# Logic_Board.net
KiCad netlist of a schematic drawn in EAGLE
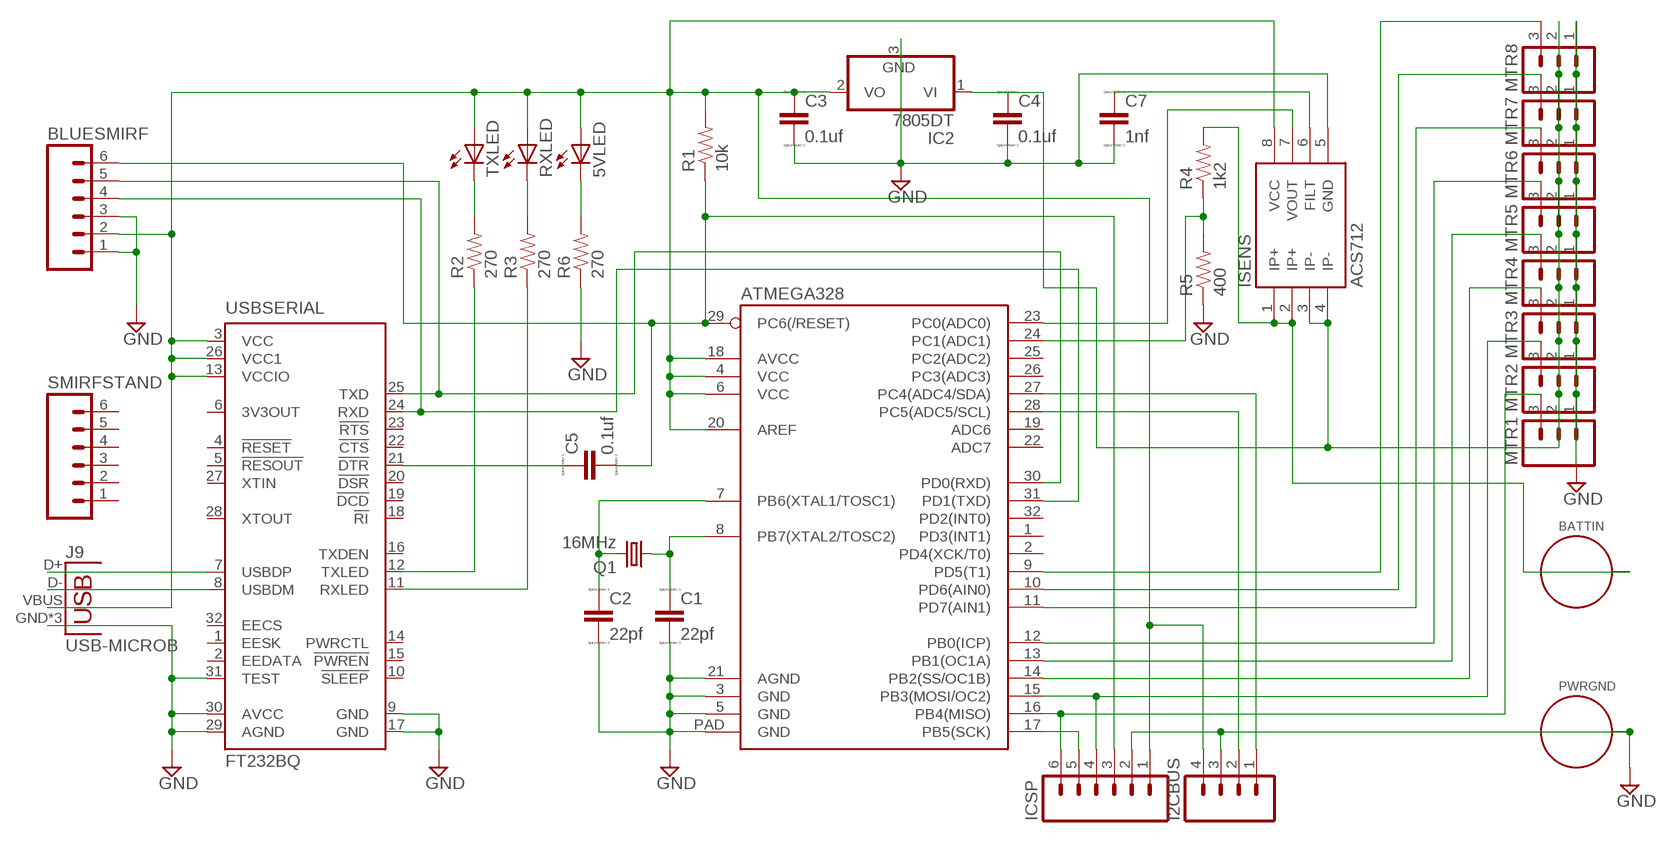
[diagram p0: schematic, sheet 1]

(export (version "E")
  (design (tool "Eeschema 10.0.6"))
  (components
    (comp (ref "5VLED")
      (value "LEDCHIPLED_0805")
      (footprint "eagle-import:CHIPLED_0805")
      (libsource (lib "eagle-import") (part "LEDCHIPLED_0805"))
    )
    (comp (ref "ATMEGA328")
      (value "ATMEGA328P_MLFMLF32")
      (footprint "eagle-import:MLF32-PAD")
      (libsource (lib "eagle-import") (part "ATMEGA328P_MLFMLF32"))
    )
    (comp (ref "BATTIN")
      (value "STANDOFF_ELECTRICAL")
      (footprint "eagle-import:STANDOFF-ELECTRICAL")
      (libsource (lib "eagle-import") (part "STANDOFF_ELECTRICAL"))
    )
    (comp (ref "BLUESMIRF")
      (value "M06NO_SILK_YES_STOP")
      (footprint "eagle-import:1X06_NO_SILK_YES_STOP")
      (libsource (lib "eagle-import") (part "M06NO_SILK_YES_STOP"))
    )
    (comp (ref "C1")
      (value "22pf")
      (footprint "eagle-import:C0805")
      (libsource (lib "eagle-import") (part "C"))
    )
    (comp (ref "C2")
      (value "22pf")
      (footprint "eagle-import:C0805")
      (libsource (lib "eagle-import") (part "C"))
    )
    (comp (ref "C3")
      (value "0.1uf")
      (footprint "eagle-import:C0805")
      (libsource (lib "eagle-import") (part "C"))
    )
    (comp (ref "C4")
      (value "0.1uf")
      (footprint "eagle-import:C0805")
      (libsource (lib "eagle-import") (part "C"))
    )
    (comp (ref "C5")
      (value "0.1uf")
      (footprint "eagle-import:C0805")
      (libsource (lib "eagle-import") (part "C"))
    )
    (comp (ref "C7")
      (value "1nf")
      (footprint "eagle-import:C0805")
      (libsource (lib "eagle-import") (part "C"))
    )
    (comp (ref "I2CBUS")
      (value "M04NO_SILK_ALL_ROUND")
      (footprint "eagle-import:1X04_NO_SILK_ALL_ROUND")
      (libsource (lib "eagle-import") (part "M04NO_SILK_ALL_ROUND"))
    )
    (comp (ref "IC2")
      (value "7805DT")
      (footprint "eagle-import:TO252")
      (libsource (lib "eagle-import") (part "78DT05"))
    )
    (comp (ref "ICSP")
      (value "M06NO_SILK_YES_STOP")
      (footprint "eagle-import:1X06_NO_SILK_YES_STOP")
      (libsource (lib "eagle-import") (part "M06NO_SILK_YES_STOP"))
    )
    (comp (ref "ISENS")
      (value "ACS712")
      (footprint "eagle-import:SO08")
      (libsource (lib "eagle-import") (part "ACS712"))
    )
    (comp (ref "J9")
      (value "USB-MICROB")
      (footprint "eagle-import:USB-MICROB")
      (libsource (lib "eagle-import") (part "USB-MICROB"))
    )
    (comp (ref "MTR1")
      (value "M03PTH")
      (footprint "eagle-import:1X03")
      (libsource (lib "eagle-import") (part "M03PTH"))
    )
    (comp (ref "MTR2")
      (value "M03PTH")
      (footprint "eagle-import:1X03")
      (libsource (lib "eagle-import") (part "M03PTH"))
    )
    (comp (ref "MTR3")
      (value "M03PTH")
      (footprint "eagle-import:1X03")
      (libsource (lib "eagle-import") (part "M03PTH"))
    )
    (comp (ref "MTR4")
      (value "M03PTH")
      (footprint "eagle-import:1X03")
      (libsource (lib "eagle-import") (part "M03PTH"))
    )
    (comp (ref "MTR5")
      (value "M03PTH")
      (footprint "eagle-import:1X03")
      (libsource (lib "eagle-import") (part "M03PTH"))
    )
    (comp (ref "MTR6")
      (value "M03PTH")
      (footprint "eagle-import:1X03")
      (libsource (lib "eagle-import") (part "M03PTH"))
    )
    (comp (ref "MTR7")
      (value "M03PTH")
      (footprint "eagle-import:1X03")
      (libsource (lib "eagle-import") (part "M03PTH"))
    )
    (comp (ref "MTR8")
      (value "M03PTH")
      (footprint "eagle-import:1X03")
      (libsource (lib "eagle-import") (part "M03PTH"))
    )
    (comp (ref "PWRGND")
      (value "STANDOFF_ELECTRICAL")
      (footprint "eagle-import:STANDOFF-ELECTRICAL")
      (libsource (lib "eagle-import") (part "STANDOFF_ELECTRICAL"))
    )
    (comp (ref "Q1")
      (value "16MHz")
      (footprint "eagle-import:HC49U-V")
      (libsource (lib "eagle-import") (part "CRYSTALHC49U-V"))
    )
    (comp (ref "R1")
      (value "10k")
      (footprint "eagle-import:0805")
      (libsource (lib "eagle-import") (part "RESISTOR0805-RES"))
    )
    (comp (ref "R2")
      (value "270")
      (footprint "eagle-import:0805")
      (libsource (lib "eagle-import") (part "RESISTOR0805-RES"))
    )
    (comp (ref "R3")
      (value "270")
      (footprint "eagle-import:0805")
      (libsource (lib "eagle-import") (part "RESISTOR0805-RES"))
    )
    (comp (ref "R4")
      (value "1k2")
      (footprint "eagle-import:0805")
      (libsource (lib "eagle-import") (part "RESISTOR0805-RES"))
    )
    (comp (ref "R5")
      (value "400")
      (footprint "eagle-import:0805")
      (libsource (lib "eagle-import") (part "RESISTOR0805-RES"))
    )
    (comp (ref "R6")
      (value "270")
      (footprint "eagle-import:0805")
      (libsource (lib "eagle-import") (part "RESISTOR0805-RES"))
    )
    (comp (ref "RXLED")
      (value "LEDCHIPLED_0805")
      (footprint "eagle-import:CHIPLED_0805")
      (libsource (lib "eagle-import") (part "LEDCHIPLED_0805"))
    )
    (comp (ref "SMIRFSTAND")
      (value "M06NO_SILK_YES_STOP")
      (footprint "eagle-import:1X06_NO_SILK_YES_STOP")
      (libsource (lib "eagle-import") (part "M06NO_SILK_YES_STOP"))
    )
    (comp (ref "TXLED")
      (value "LEDCHIPLED_0805")
      (footprint "eagle-import:CHIPLED_0805")
      (libsource (lib "eagle-import") (part "LEDCHIPLED_0805"))
    )
    (comp (ref "USBSERIAL")
      (value "FT232BQ")
      (footprint "eagle-import:QFN32")
      (libsource (lib "eagle-import") (part "FT232BQ"))
    )
  )
  (nets
    (net (code "1") (name "GND") (class "Default")
      (node (ref "ATMEGA328") (pin "21") (pinfunction "AGND_21") (pintype "bidirectional"))
      (node (ref "ATMEGA328") (pin "3") (pinfunction "GND_3") (pintype "bidirectional"))
      (node (ref "ATMEGA328") (pin "5") (pinfunction "GND_5") (pintype "bidirectional"))
      (node (ref "ATMEGA328") (pin "PAD") (pinfunction "GND_PAD") (pintype "bidirectional"))
      (node (ref "BLUESMIRF") (pin "1") (pinfunction "1_1") (pintype "passive"))
      (node (ref "BLUESMIRF") (pin "3") (pinfunction "3_3") (pintype "passive"))
      (node (ref "C1") (pin "2") (pinfunction "2_2") (pintype "passive"))
      (node (ref "C2") (pin "2") (pinfunction "2_2") (pintype "passive"))
      (node (ref "C3") (pin "2") (pinfunction "2_2") (pintype "passive"))
      (node (ref "C4") (pin "2") (pinfunction "2_2") (pintype "passive"))
      (node (ref "C7") (pin "2") (pinfunction "2_2") (pintype "passive"))
      (node (ref "I2CBUS") (pin "3") (pinfunction "3_3") (pintype "passive"))
      (node (ref "IC2") (pin "3") (pinfunction "GND_3") (pintype "passive"))
      (node (ref "ICSP") (pin "2") (pinfunction "2_2") (pintype "passive"))
      (node (ref "ISENS") (pin "5") (pinfunction "GND_5") (pintype "bidirectional"))
      (node (ref "J9") (pin "GND") (pinfunction "GND_GND") (pintype "bidirectional"))
      (node (ref "J9") (pin "MT1") (pinfunction "GND_MT1") (pintype "bidirectional"))
      (node (ref "J9") (pin "MT2") (pinfunction "GND_MT2") (pintype "bidirectional"))
      (node (ref "MTR1") (pin "1") (pinfunction "1_1") (pintype "passive"))
      (node (ref "MTR2") (pin "1") (pinfunction "1_1") (pintype "passive"))
      (node (ref "MTR3") (pin "1") (pinfunction "1_1") (pintype "passive"))
      (node (ref "MTR4") (pin "1") (pinfunction "1_1") (pintype "passive"))
      (node (ref "MTR5") (pin "1") (pinfunction "1_1") (pintype "passive"))
      (node (ref "MTR6") (pin "1") (pinfunction "1_1") (pintype "passive"))
      (node (ref "MTR7") (pin "1") (pinfunction "1_1") (pintype "passive"))
      (node (ref "MTR8") (pin "1") (pinfunction "1_1") (pintype "passive"))
      (node (ref "PWRGND") (pin "P1") (pinfunction "P$1_P1") (pintype "bidirectional"))
      (node (ref "R5") (pin "1") (pinfunction "1_1") (pintype "passive"))
      (node (ref "R6") (pin "1") (pinfunction "1_1") (pintype "passive"))
      (node (ref "USBSERIAL") (pin "17") (pinfunction "GND_17") (pintype "power_in"))
      (node (ref "USBSERIAL") (pin "29") (pinfunction "AGND_29") (pintype "power_in"))
      (node (ref "USBSERIAL") (pin "30") (pinfunction "AVCC_30") (pintype "power_in"))
      (node (ref "USBSERIAL") (pin "31") (pinfunction "TEST_31") (pintype "input"))
      (node (ref "USBSERIAL") (pin "9") (pinfunction "GND_9") (pintype "power_in"))
    )
    (net (code "2") (name "Net-(5VLED-PadC)") (class "Default")
      (node (ref "5VLED") (pin "C") (pinfunction "C_C") (pintype "passive"))
      (node (ref "R6") (pin "2") (pinfunction "2_2") (pintype "passive"))
    )
    (net (code "3") (name "Net-(ATMEGA328-AREF)") (class "Default")
      (node (ref "5VLED") (pin "A") (pinfunction "A_A") (pintype "passive"))
      (node (ref "ATMEGA328") (pin "18") (pinfunction "AVCC_18") (pintype "bidirectional"))
      (node (ref "ATMEGA328") (pin "20") (pinfunction "AREF_20") (pintype "bidirectional"))
      (node (ref "ATMEGA328") (pin "4") (pinfunction "VCC_4") (pintype "bidirectional"))
      (node (ref "ATMEGA328") (pin "6") (pinfunction "VCC_6") (pintype "bidirectional"))
      (node (ref "BLUESMIRF") (pin "2") (pinfunction "2_2") (pintype "passive"))
      (node (ref "C3") (pin "1") (pinfunction "1_1") (pintype "passive"))
      (node (ref "I2CBUS") (pin "4") (pinfunction "4_4") (pintype "passive"))
      (node (ref "IC2") (pin "2") (pinfunction "VO_2") (pintype "passive"))
      (node (ref "ICSP") (pin "1") (pinfunction "1_1") (pintype "passive"))
      (node (ref "ISENS") (pin "8") (pinfunction "VCC_8") (pintype "bidirectional"))
      (node (ref "J9") (pin "VBUS") (pinfunction "VBUS_VBUS") (pintype "bidirectional"))
      (node (ref "R1") (pin "2") (pinfunction "2_2") (pintype "passive"))
      (node (ref "RXLED") (pin "A") (pinfunction "A_A") (pintype "passive"))
      (node (ref "TXLED") (pin "A") (pinfunction "A_A") (pintype "passive"))
      (node (ref "USBSERIAL") (pin "13") (pinfunction "VCCIO_13") (pintype "power_in"))
      (node (ref "USBSERIAL") (pin "26") (pinfunction "VCC1_26") (pintype "power_in"))
      (node (ref "USBSERIAL") (pin "3") (pinfunction "VCC_3") (pintype "power_in"))
    )
    (net (code "4") (name "Net-(ATMEGA328-PB0(ICP))") (class "Default")
      (node (ref "ATMEGA328") (pin "12") (pinfunction "PB0(ICP)_12") (pintype "bidirectional"))
      (node (ref "MTR5") (pin "3") (pinfunction "3_3") (pintype "passive"))
    )
    (net (code "5") (name "Net-(ATMEGA328-PB1(OC1A))") (class "Default")
      (node (ref "ATMEGA328") (pin "13") (pinfunction "PB1(OC1A)_13") (pintype "bidirectional"))
      (node (ref "MTR4") (pin "3") (pinfunction "3_3") (pintype "passive"))
    )
    (net (code "6") (name "Net-(ATMEGA328-PB2(SS{slash}OC1B))") (class "Default")
      (node (ref "ATMEGA328") (pin "14") (pinfunction "PB2(SS/OC1B)_14") (pintype "bidirectional"))
      (node (ref "MTR3") (pin "3") (pinfunction "3_3") (pintype "passive"))
    )
    (net (code "7") (name "Net-(ATMEGA328-PB3(MOSI{slash}OC2))") (class "Default")
      (node (ref "ATMEGA328") (pin "15") (pinfunction "PB3(MOSI/OC2)_15") (pintype "bidirectional"))
      (node (ref "ICSP") (pin "4") (pinfunction "4_4") (pintype "passive"))
      (node (ref "MTR2") (pin "3") (pinfunction "3_3") (pintype "passive"))
    )
    (net (code "8") (name "Net-(ATMEGA328-PB4(MISO))") (class "Default")
      (node (ref "ATMEGA328") (pin "16") (pinfunction "PB4(MISO)_16") (pintype "bidirectional"))
      (node (ref "ICSP") (pin "6") (pinfunction "6_6") (pintype "passive"))
      (node (ref "MTR1") (pin "3") (pinfunction "3_3") (pintype "passive"))
    )
    (net (code "9") (name "Net-(ATMEGA328-PB5(SCK))") (class "Default")
      (node (ref "ATMEGA328") (pin "17") (pinfunction "PB5(SCK)_17") (pintype "bidirectional"))
      (node (ref "ICSP") (pin "5") (pinfunction "5_5") (pintype "passive"))
    )
    (net (code "10") (name "Net-(ATMEGA328-PB6(XTAL1{slash}TOSC1))") (class "Default")
      (node (ref "ATMEGA328") (pin "7") (pinfunction "PB6(XTAL1/TOSC1)_7") (pintype "bidirectional"))
      (node (ref "C2") (pin "1") (pinfunction "1_1") (pintype "passive"))
      (node (ref "Q1") (pin "2") (pinfunction "2_2") (pintype "passive"))
    )
    (net (code "11") (name "Net-(ATMEGA328-PB7(XTAL2{slash}TOSC2))") (class "Default")
      (node (ref "ATMEGA328") (pin "8") (pinfunction "PB7(XTAL2/TOSC2)_8") (pintype "bidirectional"))
      (node (ref "C1") (pin "1") (pinfunction "1_1") (pintype "passive"))
      (node (ref "Q1") (pin "1") (pinfunction "1_1") (pintype "passive"))
    )
    (net (code "12") (name "Net-(ATMEGA328-PC0(ADC0))") (class "Default")
      (node (ref "ATMEGA328") (pin "23") (pinfunction "PC0(ADC0)_23") (pintype "bidirectional"))
      (node (ref "ISENS") (pin "7") (pinfunction "VOUT_7") (pintype "bidirectional"))
    )
    (net (code "13") (name "Net-(ATMEGA328-PC1(ADC1))") (class "Default")
      (node (ref "ATMEGA328") (pin "24") (pinfunction "PC1(ADC1)_24") (pintype "bidirectional"))
      (node (ref "R4") (pin "1") (pinfunction "1_1") (pintype "passive"))
      (node (ref "R5") (pin "2") (pinfunction "2_2") (pintype "passive"))
    )
    (net (code "14") (name "Net-(ATMEGA328-PC4(ADC4{slash}SDA))") (class "Default")
      (node (ref "ATMEGA328") (pin "27") (pinfunction "PC4(ADC4/SDA)_27") (pintype "bidirectional"))
      (node (ref "I2CBUS") (pin "1") (pinfunction "1_1") (pintype "passive"))
    )
    (net (code "15") (name "Net-(ATMEGA328-PC5(ADC5{slash}SCL))") (class "Default")
      (node (ref "ATMEGA328") (pin "28") (pinfunction "PC5(ADC5/SCL)_28") (pintype "bidirectional"))
      (node (ref "I2CBUS") (pin "2") (pinfunction "2_2") (pintype "passive"))
    )
    (net (code "16") (name "Net-(ATMEGA328-PC6({slash}RESET))") (class "Default")
      (node (ref "ATMEGA328") (pin "29") (pinfunction "PC6(/RESET)_29") (pintype "bidirectional"))
      (node (ref "BLUESMIRF") (pin "6") (pinfunction "6_6") (pintype "passive"))
      (node (ref "C5") (pin "2") (pinfunction "2_2") (pintype "passive"))
      (node (ref "ICSP") (pin "3") (pinfunction "3_3") (pintype "passive"))
      (node (ref "R1") (pin "1") (pinfunction "1_1") (pintype "passive"))
    )
    (net (code "17") (name "Net-(ATMEGA328-PD0(RXD))") (class "Default")
      (node (ref "ATMEGA328") (pin "30") (pinfunction "PD0(RXD)_30") (pintype "bidirectional"))
      (node (ref "BLUESMIRF") (pin "5") (pinfunction "5_5") (pintype "passive"))
      (node (ref "USBSERIAL") (pin "25") (pinfunction "TXD_25") (pintype "output"))
    )
    (net (code "18") (name "Net-(ATMEGA328-PD1(TXD))") (class "Default")
      (node (ref "ATMEGA328") (pin "31") (pinfunction "PD1(TXD)_31") (pintype "bidirectional"))
      (node (ref "BLUESMIRF") (pin "4") (pinfunction "4_4") (pintype "passive"))
      (node (ref "USBSERIAL") (pin "24") (pinfunction "RXD_24") (pintype "input"))
    )
    (net (code "19") (name "Net-(ATMEGA328-PD5(T1))") (class "Default")
      (node (ref "ATMEGA328") (pin "9") (pinfunction "PD5(T1)_9") (pintype "bidirectional"))
      (node (ref "MTR8") (pin "3") (pinfunction "3_3") (pintype "passive"))
    )
    (net (code "20") (name "Net-(ATMEGA328-PD6(AIN0))") (class "Default")
      (node (ref "ATMEGA328") (pin "10") (pinfunction "PD6(AIN0)_10") (pintype "bidirectional"))
      (node (ref "MTR7") (pin "3") (pinfunction "3_3") (pintype "passive"))
    )
    (net (code "21") (name "Net-(ATMEGA328-PD7(AIN1))") (class "Default")
      (node (ref "ATMEGA328") (pin "11") (pinfunction "PD7(AIN1)_11") (pintype "bidirectional"))
      (node (ref "MTR6") (pin "3") (pinfunction "3_3") (pintype "passive"))
    )
    (net (code "22") (name "Net-(BATTIN-P$1)") (class "Default")
      (node (ref "BATTIN") (pin "P1") (pinfunction "P$1_P1") (pintype "bidirectional"))
      (node (ref "ISENS") (pin "1") (pinfunction "IP+_1") (pintype "bidirectional"))
      (node (ref "ISENS") (pin "2") (pinfunction "IP+_2") (pintype "bidirectional"))
      (node (ref "R4") (pin "2") (pinfunction "2_2") (pintype "passive"))
    )
    (net (code "23") (name "Net-(IC2-VI)") (class "Default")
      (node (ref "C4") (pin "1") (pinfunction "1_1") (pintype "passive"))
      (node (ref "IC2") (pin "1") (pinfunction "VI_1") (pintype "input"))
      (node (ref "ISENS") (pin "3") (pinfunction "IP-_3") (pintype "bidirectional"))
      (node (ref "ISENS") (pin "4") (pinfunction "IP-_4") (pintype "bidirectional"))
      (node (ref "MTR1") (pin "2") (pinfunction "2_2") (pintype "passive"))
      (node (ref "MTR2") (pin "2") (pinfunction "2_2") (pintype "passive"))
      (node (ref "MTR3") (pin "2") (pinfunction "2_2") (pintype "passive"))
      (node (ref "MTR4") (pin "2") (pinfunction "2_2") (pintype "passive"))
      (node (ref "MTR5") (pin "2") (pinfunction "2_2") (pintype "passive"))
      (node (ref "MTR6") (pin "2") (pinfunction "2_2") (pintype "passive"))
      (node (ref "MTR7") (pin "2") (pinfunction "2_2") (pintype "passive"))
      (node (ref "MTR8") (pin "2") (pinfunction "2_2") (pintype "passive"))
    )
    (net (code "24") (name "Net-(ISENS-FILT)") (class "Default")
      (node (ref "C7") (pin "1") (pinfunction "1_1") (pintype "passive"))
      (node (ref "ISENS") (pin "6") (pinfunction "FILT_6") (pintype "bidirectional"))
    )
    (net (code "25") (name "Net-(R2-Pad2)") (class "Default")
      (node (ref "R2") (pin "2") (pinfunction "2_2") (pintype "passive"))
      (node (ref "TXLED") (pin "C") (pinfunction "C_C") (pintype "passive"))
    )
    (net (code "26") (name "Net-(R3-Pad2)") (class "Default")
      (node (ref "R3") (pin "2") (pinfunction "2_2") (pintype "passive"))
      (node (ref "RXLED") (pin "C") (pinfunction "C_C") (pintype "passive"))
    )
    (net (code "27") (name "Net-(USBSERIAL-RXLED)") (class "Default")
      (node (ref "R3") (pin "1") (pinfunction "1_1") (pintype "passive"))
      (node (ref "USBSERIAL") (pin "11") (pinfunction "RXLED_11") (pintype "bidirectional"))
    )
    (net (code "28") (name "Net-(USBSERIAL-TXLED)") (class "Default")
      (node (ref "R2") (pin "1") (pinfunction "1_1") (pintype "passive"))
      (node (ref "USBSERIAL") (pin "12") (pinfunction "TXLED_12") (pintype "bidirectional"))
    )
    (net (code "29") (name "Net-(USBSERIAL-USBDM)") (class "Default")
      (node (ref "J9") (pin "D-") (pinfunction "D-_D-") (pintype "bidirectional"))
      (node (ref "USBSERIAL") (pin "8") (pinfunction "USBDM_8") (pintype "bidirectional"))
    )
    (net (code "30") (name "Net-(USBSERIAL-USBDP)") (class "Default")
      (node (ref "J9") (pin "D+") (pinfunction "D+_D+") (pintype "bidirectional"))
      (node (ref "USBSERIAL") (pin "7") (pinfunction "USBDP_7") (pintype "bidirectional"))
    )
    (net (code "31") (name "Net-(USBSERIAL-~{DTR})") (class "Default")
      (node (ref "C5") (pin "1") (pinfunction "1_1") (pintype "passive"))
      (node (ref "USBSERIAL") (pin "21") (pinfunction "~{DTR}_21") (pintype "output"))
    )
    (net (code "32") (name "unconnected-(ATMEGA328-ADC6-Pad19)") (class "Default")
      (node (ref "ATMEGA328") (pin "19") (pinfunction "ADC6_19") (pintype "bidirectional"))
    )
    (net (code "33") (name "unconnected-(ATMEGA328-ADC7-Pad22)") (class "Default")
      (node (ref "ATMEGA328") (pin "22") (pinfunction "ADC7_22") (pintype "bidirectional"))
    )
    (net (code "34") (name "unconnected-(ATMEGA328-PC2(ADC2)-Pad25)") (class "Default")
      (node (ref "ATMEGA328") (pin "25") (pinfunction "PC2(ADC2)_25") (pintype "bidirectional"))
    )
    (net (code "35") (name "unconnected-(ATMEGA328-PC3(ADC3)-Pad26)") (class "Default")
      (node (ref "ATMEGA328") (pin "26") (pinfunction "PC3(ADC3)_26") (pintype "bidirectional"))
    )
    (net (code "36") (name "unconnected-(ATMEGA328-PD2(INT0)-Pad32)") (class "Default")
      (node (ref "ATMEGA328") (pin "32") (pinfunction "PD2(INT0)_32") (pintype "bidirectional"))
    )
    (net (code "37") (name "unconnected-(ATMEGA328-PD3(INT1)-Pad1)") (class "Default")
      (node (ref "ATMEGA328") (pin "1") (pinfunction "PD3(INT1)_1") (pintype "bidirectional"))
    )
    (net (code "38") (name "unconnected-(ATMEGA328-PD4(XCK{slash}T0)-Pad2)") (class "Default")
      (node (ref "ATMEGA328") (pin "2") (pinfunction "PD4(XCK/T0)_2") (pintype "bidirectional"))
    )
    (net (code "39") (name "unconnected-(SMIRFSTAND-Pad1)") (class "Default")
      (node (ref "SMIRFSTAND") (pin "1") (pinfunction "1_1") (pintype "passive"))
    )
    (net (code "40") (name "unconnected-(SMIRFSTAND-Pad2)") (class "Default")
      (node (ref "SMIRFSTAND") (pin "2") (pinfunction "2_2") (pintype "passive"))
    )
    (net (code "41") (name "unconnected-(SMIRFSTAND-Pad3)") (class "Default")
      (node (ref "SMIRFSTAND") (pin "3") (pinfunction "3_3") (pintype "passive"))
    )
    (net (code "42") (name "unconnected-(SMIRFSTAND-Pad4)") (class "Default")
      (node (ref "SMIRFSTAND") (pin "4") (pinfunction "4_4") (pintype "passive"))
    )
    (net (code "43") (name "unconnected-(SMIRFSTAND-Pad5)") (class "Default")
      (node (ref "SMIRFSTAND") (pin "5") (pinfunction "5_5") (pintype "passive"))
    )
    (net (code "44") (name "unconnected-(SMIRFSTAND-Pad6)") (class "Default")
      (node (ref "SMIRFSTAND") (pin "6") (pinfunction "6_6") (pintype "passive"))
    )
    (net (code "45") (name "unconnected-(USBSERIAL-3V3OUT-Pad6)") (class "Default")
      (node (ref "USBSERIAL") (pin "6") (pinfunction "3V3OUT_6") (pintype "output"))
    )
    (net (code "46") (name "unconnected-(USBSERIAL-EECS-Pad32)") (class "Default")
      (node (ref "USBSERIAL") (pin "32") (pinfunction "EECS_32") (pintype "input"))
    )
    (net (code "47") (name "unconnected-(USBSERIAL-EEDATA-Pad2)") (class "Default")
      (node (ref "USBSERIAL") (pin "2") (pinfunction "EEDATA_2") (pintype "input"))
    )
    (net (code "48") (name "unconnected-(USBSERIAL-EESK-Pad1)") (class "Default")
      (node (ref "USBSERIAL") (pin "1") (pinfunction "EESK_1") (pintype "input"))
    )
    (net (code "49") (name "unconnected-(USBSERIAL-PWRCTL-Pad14)") (class "Default")
      (node (ref "USBSERIAL") (pin "14") (pinfunction "PWRCTL_14") (pintype "bidirectional"))
    )
    (net (code "50") (name "unconnected-(USBSERIAL-TXDEN-Pad16)") (class "Default")
      (node (ref "USBSERIAL") (pin "16") (pinfunction "TXDEN_16") (pintype "bidirectional"))
    )
    (net (code "51") (name "unconnected-(USBSERIAL-XTIN-Pad27)") (class "Default")
      (node (ref "USBSERIAL") (pin "27") (pinfunction "XTIN_27") (pintype "input"))
    )
    (net (code "52") (name "unconnected-(USBSERIAL-XTOUT-Pad28)") (class "Default")
      (node (ref "USBSERIAL") (pin "28") (pinfunction "XTOUT_28") (pintype "output"))
    )
    (net (code "53") (name "unconnected-(USBSERIAL-~{CTS}-Pad22)") (class "Default")
      (node (ref "USBSERIAL") (pin "22") (pinfunction "~{CTS}_22") (pintype "input"))
    )
    (net (code "54") (name "unconnected-(USBSERIAL-~{DCD}-Pad19)") (class "Default")
      (node (ref "USBSERIAL") (pin "19") (pinfunction "~{DCD}_19") (pintype "input"))
    )
    (net (code "55") (name "unconnected-(USBSERIAL-~{DSR}-Pad20)") (class "Default")
      (node (ref "USBSERIAL") (pin "20") (pinfunction "~{DSR}_20") (pintype "input"))
    )
    (net (code "56") (name "unconnected-(USBSERIAL-~{PWREN}-Pad15)") (class "Default")
      (node (ref "USBSERIAL") (pin "15") (pinfunction "~{PWREN}_15") (pintype "bidirectional"))
    )
    (net (code "57") (name "unconnected-(USBSERIAL-~{RESET}-Pad4)") (class "Default")
      (node (ref "USBSERIAL") (pin "4") (pinfunction "~{RESET}_4") (pintype "input"))
    )
    (net (code "58") (name "unconnected-(USBSERIAL-~{RESOUT}-Pad5)") (class "Default")
      (node (ref "USBSERIAL") (pin "5") (pinfunction "~{RESOUT}_5") (pintype "input"))
    )
    (net (code "59") (name "unconnected-(USBSERIAL-~{RI}-Pad18)") (class "Default")
      (node (ref "USBSERIAL") (pin "18") (pinfunction "~{RI}_18") (pintype "input"))
    )
    (net (code "60") (name "unconnected-(USBSERIAL-~{RTS}-Pad23)") (class "Default")
      (node (ref "USBSERIAL") (pin "23") (pinfunction "~{RTS}_23") (pintype "output"))
    )
    (net (code "61") (name "unconnected-(USBSERIAL-~{SLEEP}-Pad10)") (class "Default")
      (node (ref "USBSERIAL") (pin "10") (pinfunction "~{SLEEP}_10") (pintype "input"))
    )
  )
)
